# Un_TTL_2.net
KiCad netlist of a schematic drawn in EAGLE
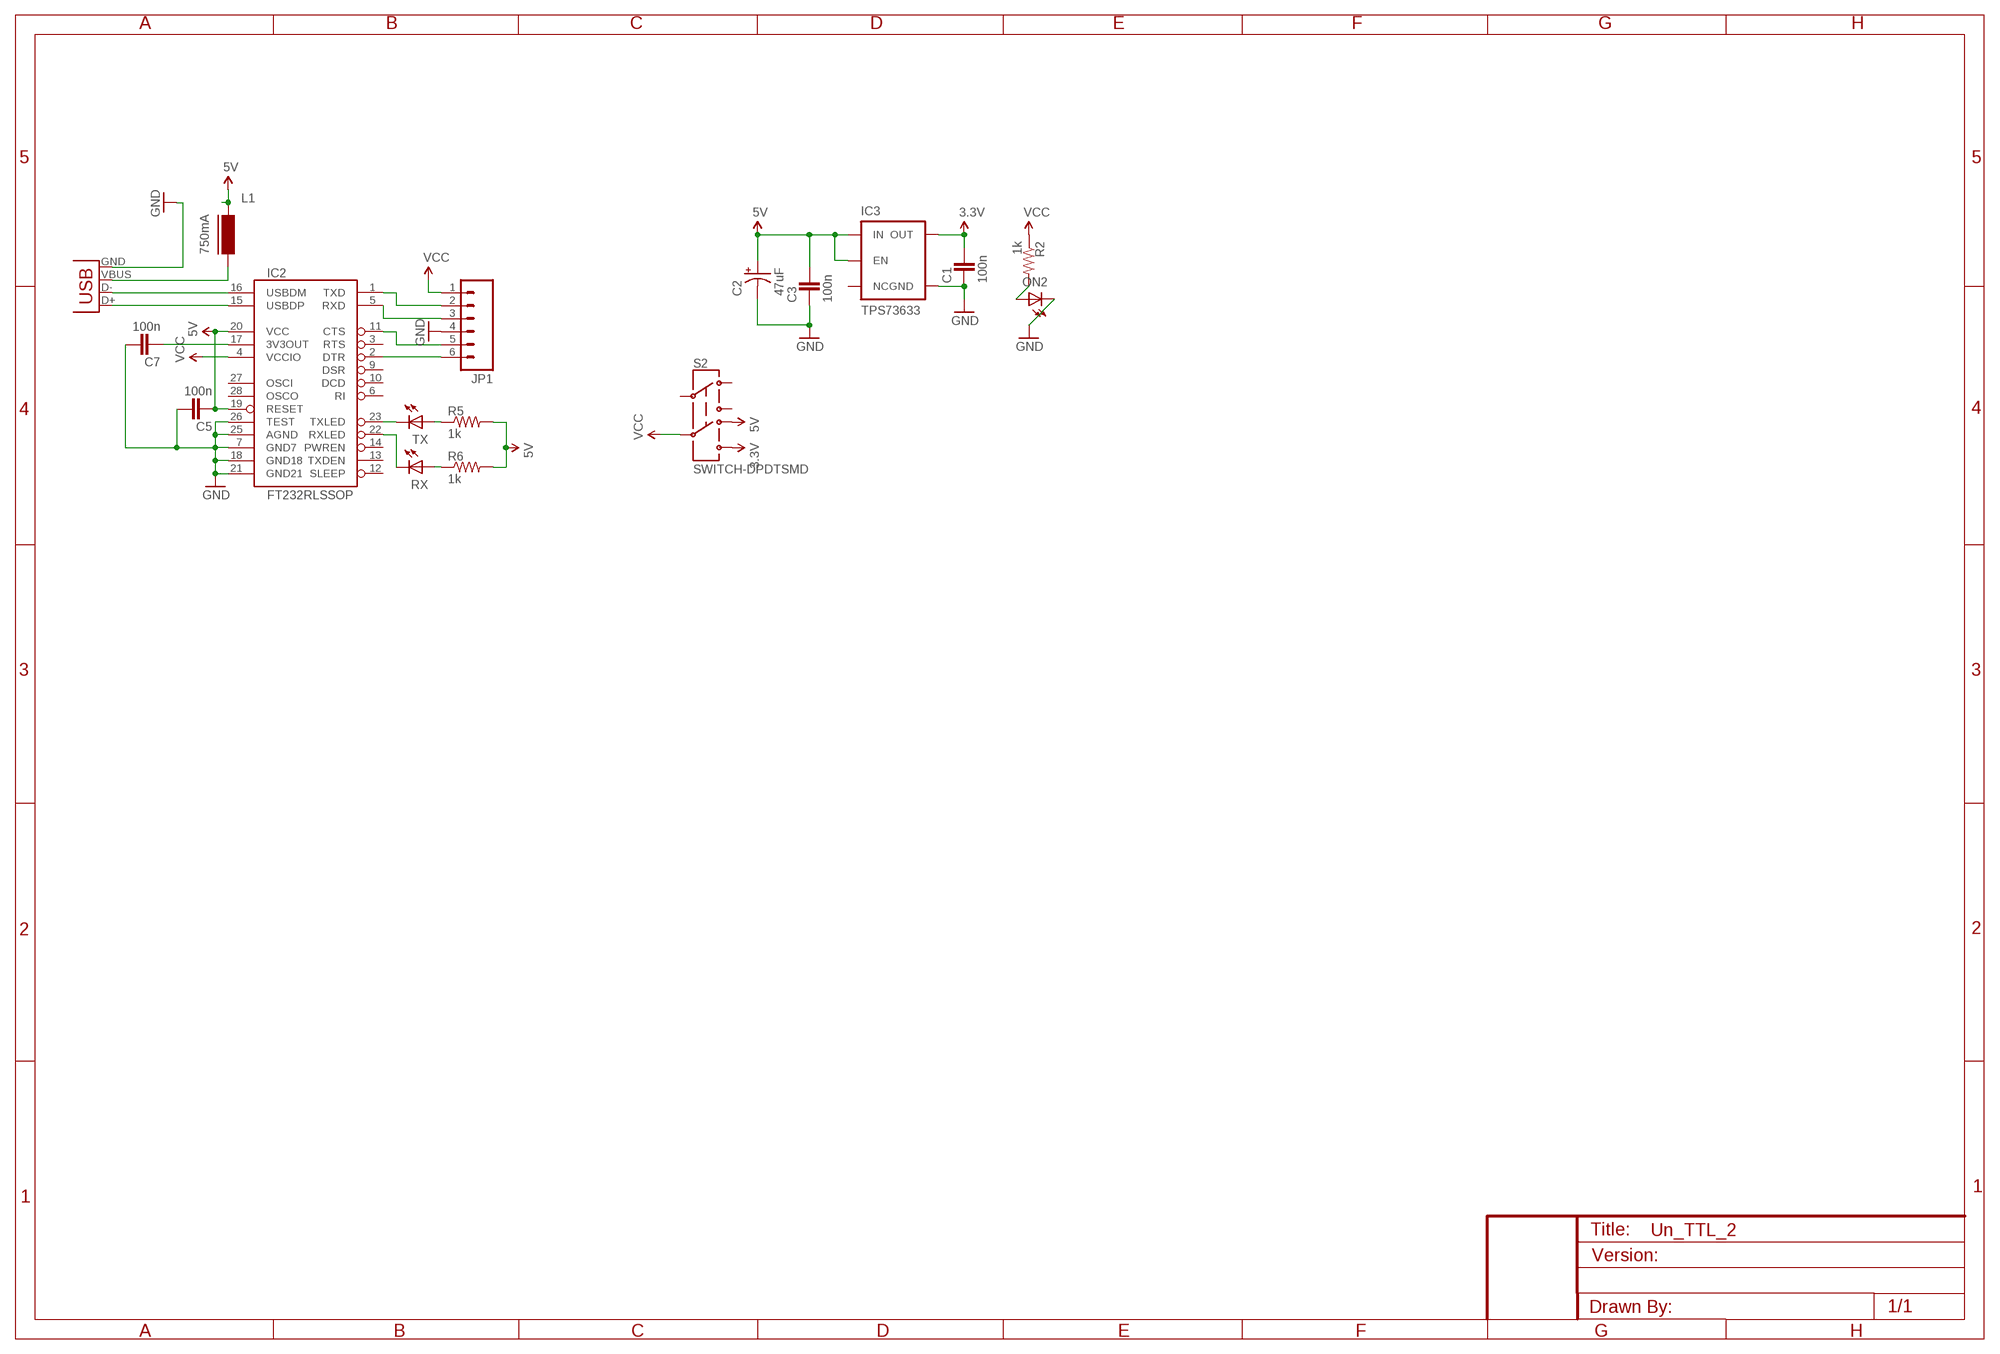
[diagram p0: schematic, sheet 1]

(export (version "E")
  (design (tool "Eeschema 10.0.6"))
  (components
    (comp (ref "C1")
      (value "100n")
      (footprint "eagle-import:0603-CAP")
      (libsource (lib "eagle-import") (part "CAP0603"))
    )
    (comp (ref "C2")
      (value "47uF")
      (footprint "eagle-import:EIA3216")
      (libsource (lib "eagle-import") (part "CAP_POL1206"))
    )
    (comp (ref "C3")
      (value "100n")
      (footprint "eagle-import:0603-CAP")
      (libsource (lib "eagle-import") (part "CAP0603"))
    )
    (comp (ref "C5")
      (value "100n")
      (footprint "eagle-import:0603-CAP")
      (libsource (lib "eagle-import") (part "CAP0603"))
    )
    (comp (ref "C7")
      (value "100n")
      (footprint "eagle-import:0603-CAP")
      (libsource (lib "eagle-import") (part "CAP0603"))
    )
    (comp (ref "IC2")
      (value "FT232RLSSOP")
      (footprint "eagle-import:SSOP28DB")
      (libsource (lib "eagle-import") (part "FT232RLSSOP"))
    )
    (comp (ref "IC3")
      (value "TPS73633")
      (footprint "eagle-import:SOT23-5")
      (libsource (lib "eagle-import") (part "V_REG_TPS76433SOT23-5"))
    )
    (comp (ref "JP1")
      (value "M06SIP")
      (footprint "eagle-import:1X06")
      (libsource (lib "eagle-import") (part "M06SIP"))
    )
    (comp (ref "L1")
      (value "750mA")
      (footprint "eagle-import:FB805")
      (libsource (lib "eagle-import") (part "FERRITE-0805"))
    )
    (comp (ref "ON2")
      (value "LED0603")
      (footprint "eagle-import:LED-0603")
      (libsource (lib "eagle-import") (part "LED0603"))
    )
    (comp (ref "R2")
      (value "1k")
      (footprint "eagle-import:0603-RES")
      (libsource (lib "eagle-import") (part "RESISTOR0603-RES"))
    )
    (comp (ref "R5")
      (value "1k")
      (footprint "eagle-import:0603-RES")
      (libsource (lib "eagle-import") (part "RESISTOR0603-RES"))
    )
    (comp (ref "R6")
      (value "1k")
      (footprint "eagle-import:0603-RES")
      (libsource (lib "eagle-import") (part "RESISTOR0603-RES"))
    )
    (comp (ref "RX")
      (value "LED0603")
      (footprint "eagle-import:LED-0603")
      (libsource (lib "eagle-import") (part "LED0603"))
    )
    (comp (ref "S2")
      (value "SWITCH-DPDTSMD")
      (footprint "eagle-import:AYZ0202")
      (libsource (lib "eagle-import") (part "SWITCH-DPDTSMD"))
    )
    (comp (ref "TX")
      (value "LED0603")
      (footprint "eagle-import:LED-0603")
      (libsource (lib "eagle-import") (part "LED0603"))
    )
    (comp (ref "X2")
      (value "USB_4-A-H")
      (footprint "eagle-import:USB-A-H")
      (libsource (lib "eagle-import") (part "USB_4-A-H"))
    )
  )
  (nets
    (net (code "1") (name "3.3V") (class "Default")
      (node (ref "C1") (pin "1") (pinfunction "1_1") (pintype "passive"))
      (node (ref "IC3") (pin "5") (pinfunction "OUT_5") (pintype "passive"))
      (node (ref "S2") (pin "6") (pinfunction "6_6") (pintype "bidirectional"))
    )
    (net (code "2") (name "5V") (class "Default")
      (node (ref "C2") (pin "A") (pinfunction "+_A") (pintype "passive"))
      (node (ref "C3") (pin "1") (pinfunction "1_1") (pintype "passive"))
      (node (ref "C5") (pin "2") (pinfunction "2_2") (pintype "passive"))
      (node (ref "IC2") (pin "19") (pinfunction "RESET_19") (pintype "input"))
      (node (ref "IC2") (pin "20") (pinfunction "VCC_20") (pintype "power_in"))
      (node (ref "IC3") (pin "1") (pinfunction "IN_1") (pintype "input"))
      (node (ref "IC3") (pin "3") (pinfunction "EN_3") (pintype "input"))
      (node (ref "L1") (pin "1") (pinfunction "1_1") (pintype "passive"))
      (node (ref "R5") (pin "2") (pinfunction "2_2") (pintype "passive"))
      (node (ref "R6") (pin "2") (pinfunction "2_2") (pintype "passive"))
      (node (ref "S2") (pin "4") (pinfunction "4_4") (pintype "bidirectional"))
    )
    (net (code "3") (name "GND") (class "Default")
      (node (ref "C1") (pin "2") (pinfunction "2_2") (pintype "passive"))
      (node (ref "C2") (pin "C") (pinfunction "-_C") (pintype "passive"))
      (node (ref "C3") (pin "2") (pinfunction "2_2") (pintype "passive"))
      (node (ref "C5") (pin "1") (pinfunction "1_1") (pintype "passive"))
      (node (ref "C7") (pin "1") (pinfunction "1_1") (pintype "passive"))
      (node (ref "IC2") (pin "18") (pinfunction "GND18_18") (pintype "power_in"))
      (node (ref "IC2") (pin "21") (pinfunction "GND21_21") (pintype "power_in"))
      (node (ref "IC2") (pin "25") (pinfunction "AGND_25") (pintype "power_in"))
      (node (ref "IC2") (pin "26") (pinfunction "TEST_26") (pintype "input"))
      (node (ref "IC2") (pin "7") (pinfunction "GND7_7") (pintype "power_in"))
      (node (ref "IC3") (pin "2") (pinfunction "GND_2") (pintype "input"))
      (node (ref "JP1") (pin "4") (pinfunction "4_4") (pintype "passive"))
      (node (ref "ON2") (pin "C") (pinfunction "C_C") (pintype "passive"))
      (node (ref "X2") (pin "GND") (pinfunction "GND_GND") (pintype "bidirectional"))
    )
    (net (code "4") (name "Net-(IC2-3V3OUT)") (class "Default")
      (node (ref "C7") (pin "2") (pinfunction "2_2") (pintype "passive"))
      (node (ref "IC2") (pin "17") (pinfunction "3V3OUT_17") (pintype "output"))
    )
    (net (code "5") (name "Net-(IC2-CTS)") (class "Default")
      (node (ref "IC2") (pin "11") (pinfunction "CTS_11") (pintype "input"))
      (node (ref "JP1") (pin "5") (pinfunction "5_5") (pintype "passive"))
    )
    (net (code "6") (name "Net-(IC2-DTR)") (class "Default")
      (node (ref "IC2") (pin "2") (pinfunction "DTR_2") (pintype "output"))
      (node (ref "JP1") (pin "6") (pinfunction "6_6") (pintype "passive"))
    )
    (net (code "7") (name "Net-(IC2-RXD)") (class "Default")
      (node (ref "IC2") (pin "5") (pinfunction "RXD_5") (pintype "input"))
      (node (ref "JP1") (pin "3") (pinfunction "3_3") (pintype "passive"))
    )
    (net (code "8") (name "Net-(IC2-RXLED)") (class "Default")
      (node (ref "IC2") (pin "22") (pinfunction "RXLED_22") (pintype "input"))
      (node (ref "RX") (pin "C") (pinfunction "C_C") (pintype "passive"))
    )
    (net (code "9") (name "Net-(IC2-TXD)") (class "Default")
      (node (ref "IC2") (pin "1") (pinfunction "TXD_1") (pintype "output"))
      (node (ref "JP1") (pin "2") (pinfunction "2_2") (pintype "passive"))
    )
    (net (code "10") (name "Net-(IC2-TXLED)") (class "Default")
      (node (ref "IC2") (pin "23") (pinfunction "TXLED_23") (pintype "input"))
      (node (ref "TX") (pin "C") (pinfunction "C_C") (pintype "passive"))
    )
    (net (code "11") (name "Net-(IC2-USBDM)") (class "Default")
      (node (ref "IC2") (pin "16") (pinfunction "USBDM_16") (pintype "bidirectional"))
      (node (ref "X2") (pin "D-") (pinfunction "D-_D-") (pintype "bidirectional"))
    )
    (net (code "12") (name "Net-(IC2-USBDP)") (class "Default")
      (node (ref "IC2") (pin "15") (pinfunction "USBDP_15") (pintype "bidirectional"))
      (node (ref "X2") (pin "D+") (pinfunction "D+_D+") (pintype "bidirectional"))
    )
    (net (code "13") (name "Net-(L1-Pad2)") (class "Default")
      (node (ref "L1") (pin "2") (pinfunction "2_2") (pintype "passive"))
      (node (ref "X2") (pin "VBUS") (pinfunction "VBUS_VBUS") (pintype "bidirectional"))
    )
    (net (code "14") (name "Net-(ON2-PadA)") (class "Default")
      (node (ref "ON2") (pin "A") (pinfunction "A_A") (pintype "passive"))
      (node (ref "R2") (pin "2") (pinfunction "2_2") (pintype "passive"))
    )
    (net (code "15") (name "Net-(R5-Pad1)") (class "Default")
      (node (ref "R5") (pin "1") (pinfunction "1_1") (pintype "passive"))
      (node (ref "TX") (pin "A") (pinfunction "A_A") (pintype "passive"))
    )
    (net (code "16") (name "Net-(R6-Pad1)") (class "Default")
      (node (ref "R6") (pin "1") (pinfunction "1_1") (pintype "passive"))
      (node (ref "RX") (pin "A") (pinfunction "A_A") (pintype "passive"))
    )
    (net (code "17") (name "VCC") (class "Default")
      (node (ref "IC2") (pin "4") (pinfunction "VCCIO_4") (pintype "power_in"))
      (node (ref "JP1") (pin "1") (pinfunction "1_1") (pintype "passive"))
      (node (ref "R2") (pin "1") (pinfunction "1_1") (pintype "passive"))
      (node (ref "S2") (pin "5") (pinfunction "5_5") (pintype "bidirectional"))
    )
    (net (code "18") (name "unconnected-(IC2-DCD-Pad10)") (class "Default")
      (node (ref "IC2") (pin "10") (pinfunction "DCD_10") (pintype "input"))
    )
    (net (code "19") (name "unconnected-(IC2-DSR-Pad9)") (class "Default")
      (node (ref "IC2") (pin "9") (pinfunction "DSR_9") (pintype "input"))
    )
    (net (code "20") (name "unconnected-(IC2-OSCI-Pad27)") (class "Default")
      (node (ref "IC2") (pin "27") (pinfunction "OSCI_27") (pintype "input"))
    )
    (net (code "21") (name "unconnected-(IC2-OSCO-Pad28)") (class "Default")
      (node (ref "IC2") (pin "28") (pinfunction "OSCO_28") (pintype "output"))
    )
    (net (code "22") (name "unconnected-(IC2-PWREN-Pad14)") (class "Default")
      (node (ref "IC2") (pin "14") (pinfunction "PWREN_14") (pintype "input"))
    )
    (net (code "23") (name "unconnected-(IC2-RI-Pad6)") (class "Default")
      (node (ref "IC2") (pin "6") (pinfunction "RI_6") (pintype "input"))
    )
    (net (code "24") (name "unconnected-(IC2-RTS-Pad3)") (class "Default")
      (node (ref "IC2") (pin "3") (pinfunction "RTS_3") (pintype "output"))
    )
    (net (code "25") (name "unconnected-(IC2-SLEEP-Pad12)") (class "Default")
      (node (ref "IC2") (pin "12") (pinfunction "SLEEP_12") (pintype "input"))
    )
    (net (code "26") (name "unconnected-(IC2-TXDEN-Pad13)") (class "Default")
      (node (ref "IC2") (pin "13") (pinfunction "TXDEN_13") (pintype "input"))
    )
    (net (code "27") (name "unconnected-(IC3-NC-Pad4)") (class "Default")
      (node (ref "IC3") (pin "4") (pinfunction "NC_4") (pintype "input"))
    )
    (net (code "28") (name "unconnected-(S2-Pad1)") (class "Default")
      (node (ref "S2") (pin "1") (pinfunction "1_1") (pintype "bidirectional"))
    )
    (net (code "29") (name "unconnected-(S2-Pad2)") (class "Default")
      (node (ref "S2") (pin "2") (pinfunction "2_2") (pintype "bidirectional"))
    )
    (net (code "30") (name "unconnected-(S2-Pad3)") (class "Default")
      (node (ref "S2") (pin "3") (pinfunction "3_3") (pintype "bidirectional"))
    )
  )
)
